# HDMI.net
KiCad netlist of a schematic drawn in Altium Designer
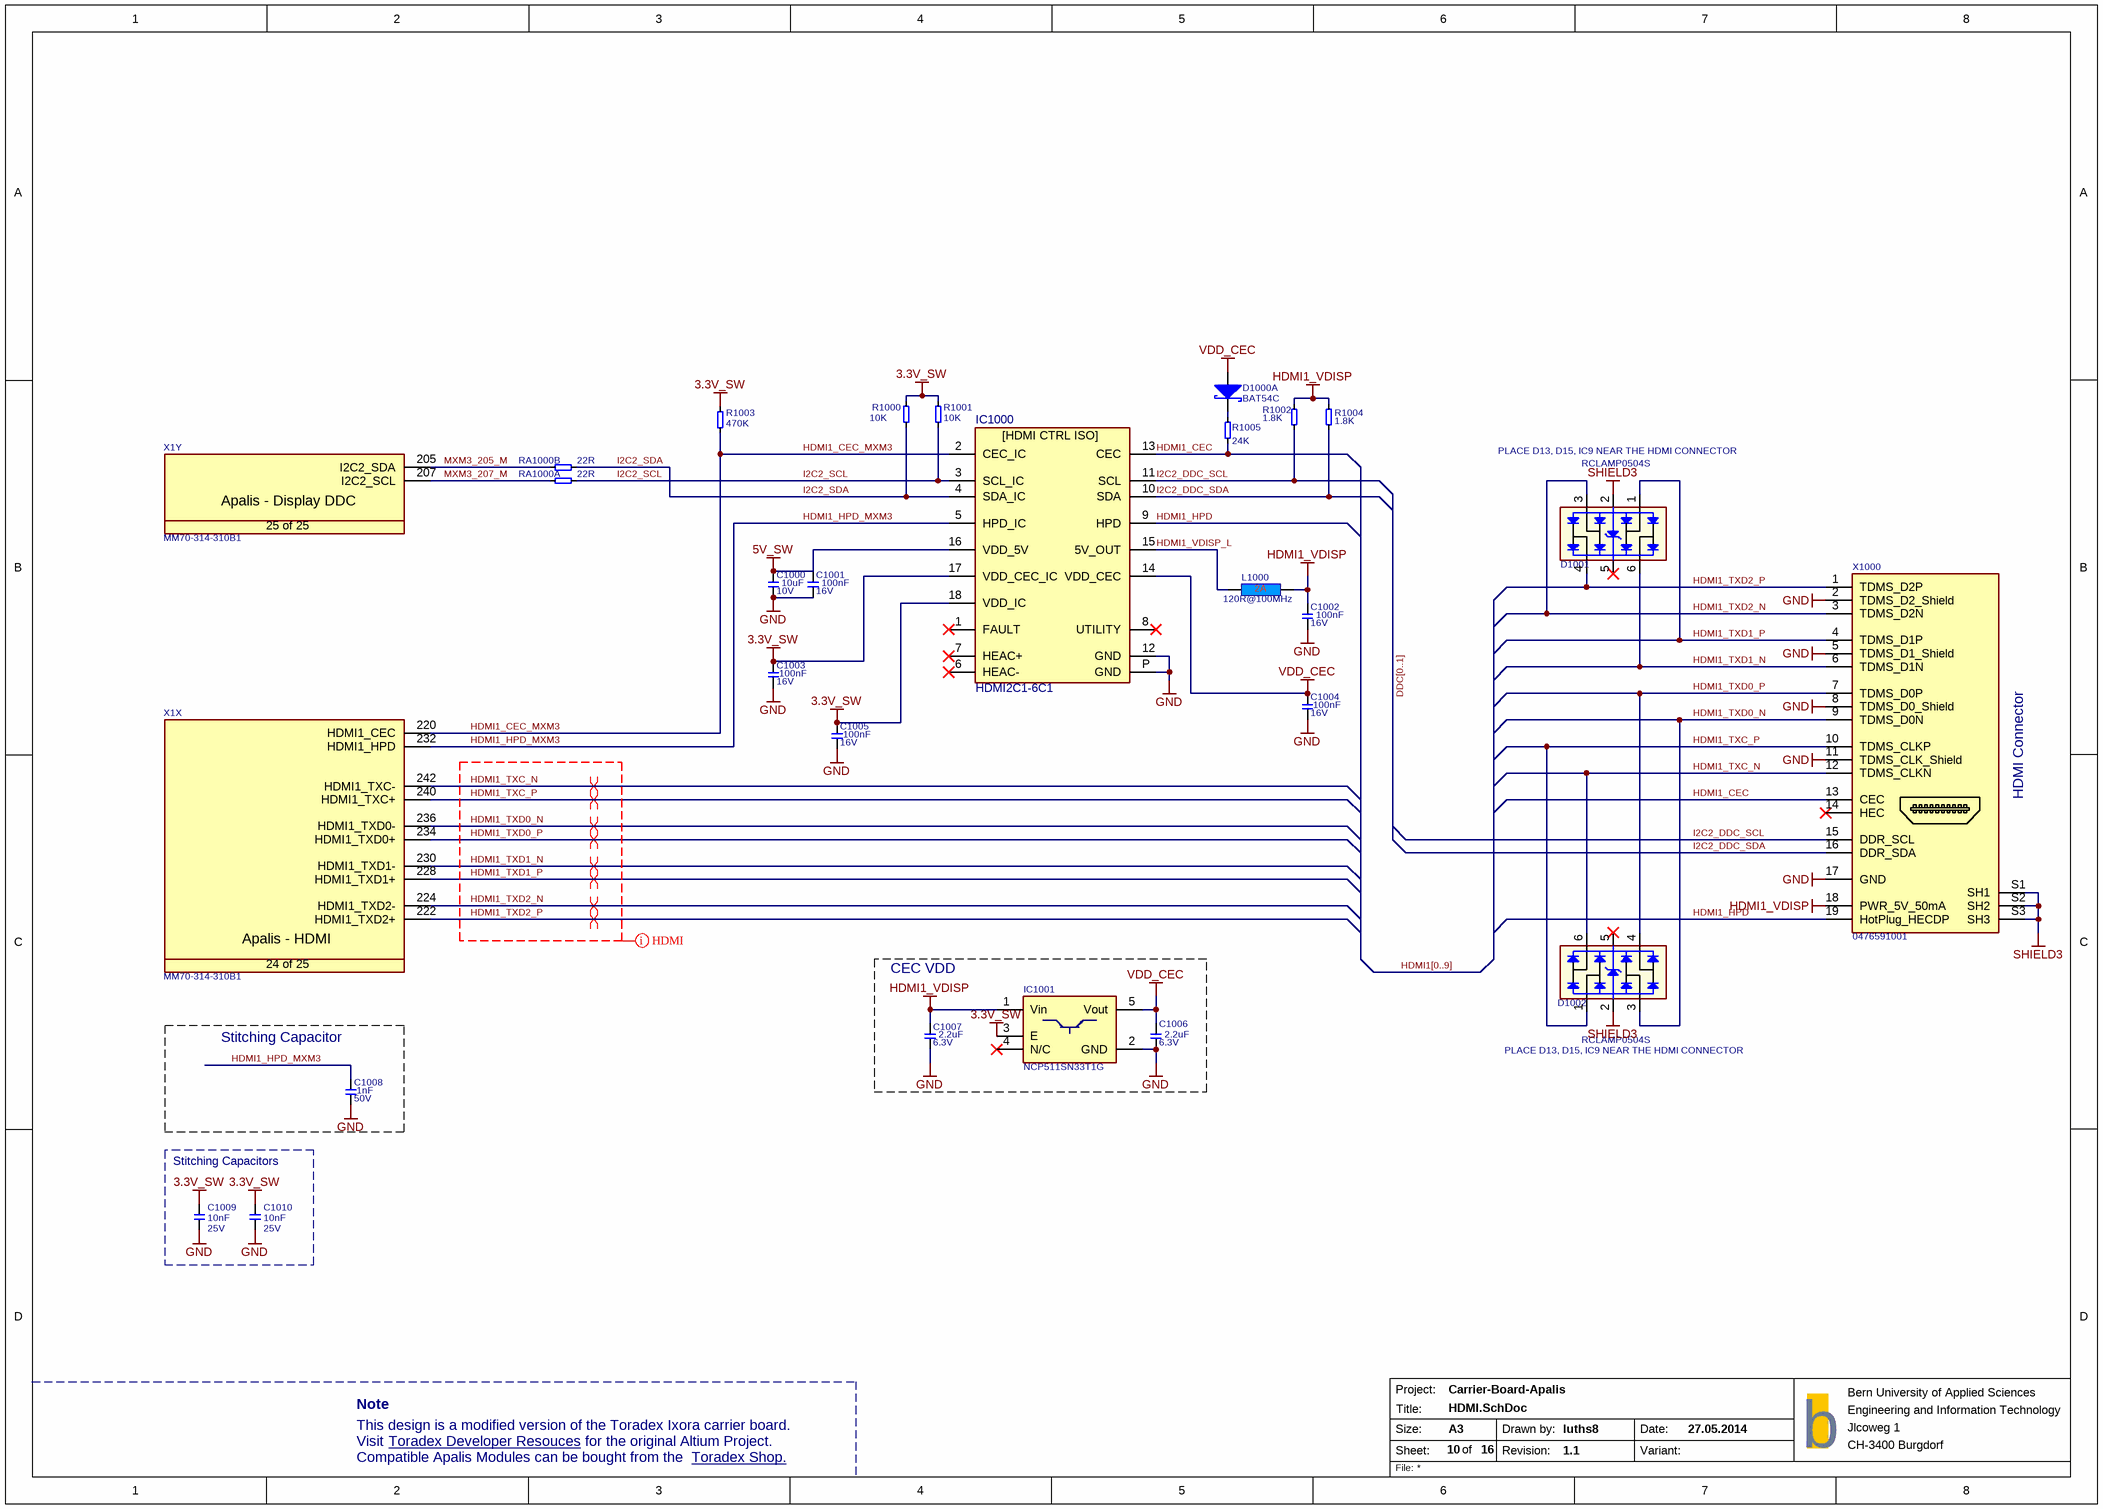
[diagram p0: HDMI.SchDoc]

(export (version "E")
  (design (tool "Eeschema 10.0.6"))
  (components
    (comp (ref "C1000")
      (value "10uF")
      (footprint "SMD0603CAP")
      (description "Capacitor Ceramic X5R 10uF 10V 20% 0603")
      (fields (field (name "TOLERANCE") "20%") (field (name "RATING") "10V"))
      (libsource (lib "Ixora") (part "C-X5R-10uF-10V-20%-0603"))
    )
    (comp (ref "C1001")
      (value "100nF")
      (footprint "SMD0603CAP")
      (description "Capacitor Ceramic X7R 100nF 16V 10% 0603")
      (fields (field (name "TOLERANCE") "10%") (field (name "RATING") "16V"))
      (libsource (lib "") (part "C-X7R-100nF-16V-10%-0402_1"))
    )
    (comp (ref "C1002")
      (value "100nF")
      (footprint "SMD0603CAP")
      (description "Capacitor Ceramic X7R 100nF 16V 10% 0603")
      (fields (field (name "TOLERANCE") "10%") (field (name "RATING") "16V"))
      (libsource (lib "Ixora") (part "C-X7R-100nF-16V-10%-0402"))
    )
    (comp (ref "C1003")
      (value "100nF")
      (footprint "SMD0603CAP")
      (description "Capacitor Ceramic X7R 100nF 16V 10% 0603")
      (fields (field (name "TOLERANCE") "10%") (field (name "RATING") "16V"))
      (libsource (lib "Ixora") (part "C-X7R-100nF-16V-10%-0402"))
    )
    (comp (ref "C1004")
      (value "100nF")
      (footprint "SMD0603CAP")
      (description "Capacitor Ceramic X7R 100nF 16V 10% 0603")
      (fields (field (name "TOLERANCE") "10%") (field (name "RATING") "16V"))
      (libsource (lib "Ixora") (part "C-X7R-100nF-16V-10%-0402"))
    )
    (comp (ref "C1005")
      (value "100nF")
      (footprint "SMD0603CAP")
      (description "Capacitor Ceramic X7R 100nF 16V 10% 0603")
      (fields (field (name "TOLERANCE") "10%") (field (name "RATING") "16V"))
      (libsource (lib "Ixora") (part "C-X7R-100nF-16V-10%-0402"))
    )
    (comp (ref "C1006")
      (value "2.2uF")
      (footprint "SMD0603CAP")
      (description "Capacitor Ceramic X5R 2.2uF 6.3V 20% 0603")
      (fields (field (name "TOLERANCE") "20%") (field (name "RATING") "6.3V"))
      (libsource (lib "Ixora") (part "C-X5R-2.2uF-6.3V-20%-0603"))
    )
    (comp (ref "C1007")
      (value "2.2uF")
      (footprint "SMD0603CAP")
      (description "Capacitor Ceramic X5R 2.2uF 6.3V 20% 0603")
      (fields (field (name "TOLERANCE") "20%") (field (name "RATING") "6.3V"))
      (libsource (lib "Ixora") (part "C-X5R-2.2uF-6.3V-20%-0603"))
    )
    (comp (ref "C1008")
      (value "1nF")
      (footprint "SMD0603CAP")
      (description "Capacitor Ceramic X7R 1nF 50V 10% 0603")
      (fields (field (name "TOLERANCE") "10%") (field (name "RATING") "50V"))
      (libsource (lib "Ixora") (part "C-X7R-1nF-50V-10%-0402"))
    )
    (comp (ref "C1009")
      (value "10nF")
      (footprint "SMD0603CAP")
      (description "Capacitor Ceramic X7R 10nF 25V 10% 0603")
      (fields (field (name "TOLERANCE") "10%") (field (name "RATING") "25V"))
      (libsource (lib "Ixora") (part "C-X7R-10nF-25V-10%-0603"))
    )
    (comp (ref "C1010")
      (value "10nF")
      (footprint "SMD0603CAP")
      (description "Capacitor Ceramic X7R 10nF 25V 10% 0603")
      (fields (field (name "TOLERANCE") "10%") (field (name "RATING") "25V"))
      (libsource (lib "Ixora") (part "C-X7R-10nF-25V-10%-0603"))
    )
    (comp (ref "D1000")
      (value "BAT54C")
      (footprint "SOT95P230X110-3N")
      (description "BAT54 Schottky Diode")
      (fields (field (name "MANUFACTURER") "Philips") (field (name "MANUFACTURER PART NUMBER") "BAT54C"))
      (libsource (lib "Ixora") (part "D-Philips-BAT54C-Schottky-30V-200mA"))
    )
    (comp (ref "D1001")
      (value "RCLAMP0504S")
      (footprint "T_SOT95P285X90-6N")
      (description "TVS Array low cap")
      (fields (field (name "MANUFACTURER PART NO.") "RCLAMP0504S"))
      (libsource (lib "") (part "D-Semtech-RClamp0504S_1"))
    )
    (comp (ref "D1002")
      (value "RCLAMP0504S")
      (footprint "T_SOT95P285X90-6N")
      (description "TVS Array low cap")
      (fields (field (name "MANUFACTURER PART NO.") "RCLAMP0504S"))
      (libsource (lib "Ixora") (part "D-Semtech-RClamp0504S"))
    )
    (comp (ref "IC1000")
      (value "HDMI2C1-6C1")
      (footprint "QFN18")
      (description "HDMI ESD protection, level shifter and backdrive protection")
      (libsource (lib "Audio-Streamer") (part "HDMI2C1-6C1"))
    )
    (comp (ref "IC1001")
      (value "NCP511SN33T1G")
      (footprint "SOT95P279X142-5N")
      (description "NCP511SN33T1G LDO Regulator")
      (fields (field (name "MANUFACTURER PART NO.") "NCP511SN33T1G"))
      (libsource (lib "Ixora") (part "IC-ON-NCP511SN33T1G"))
    )
    (comp (ref "L1000")
      (value "120R@100MHz")
      (footprint "INDC1608X95N")
      (description "120R@100MHz 2A EMI FILTER")
      (fields (field (name "TOLERANCE") "25%"))
      (libsource (lib "Ixora") (part "L-120R@100MHz-2A-25%-0603"))
    )
    (comp (ref "R1000")
      (value "10K")
      (footprint "SMD0603RES")
      (description "Resistor 10 Kohm 63mW 1% 0603")
      (fields (field (name "TOLERANCE") "1%"))
      (libsource (lib "Ixora") (part "R-10KR-63mW-1%-0603"))
    )
    (comp (ref "R1001")
      (value "10K")
      (footprint "SMD0603RES")
      (description "Resistor 10 Kohm 63mW 1% 0603")
      (fields (field (name "TOLERANCE") "1%"))
      (libsource (lib "Ixora") (part "R-10KR-63mW-1%-0603"))
    )
    (comp (ref "R1002")
      (value "1.8K")
      (footprint "SMD0603RES")
      (description "Resistor 1.8 Kohm 63mW 5% 0603")
      (fields (field (name "TOLERANCE") "5%"))
      (libsource (lib "Ixora") (part "R-1.8KR-63mW-5%-0603"))
    )
    (comp (ref "R1003")
      (value "470K")
      (footprint "SMD0603RES")
      (description "Resistor 470 Kohm 63mW 5% 0603")
      (fields (field (name "TOLERANCE") "5%"))
      (libsource (lib "Ixora") (part "R-470KR-63mW-5%-0402"))
    )
    (comp (ref "R1004")
      (value "1.8K")
      (footprint "SMD0603RES")
      (description "Resistor 1.8 Kohm 63mW 5% 0603")
      (fields (field (name "TOLERANCE") "5%"))
      (libsource (lib "Ixora") (part "R-1.8KR-63mW-5%-0603"))
    )
    (comp (ref "R1005")
      (value "24K")
      (footprint "SMD0603RES")
      (description "Resistor 24 Kohm 63mW 1% 0603")
      (fields (field (name "TOLERANCE") "1%"))
      (libsource (lib "Ixora") (part "R-24KR-63mW-1%-0402"))
    )
    (comp (ref "RA1000")
      (value "22R")
      (footprint "T_Resistor_Array_X4")
      (description "Resistor Array 22 R 63mW 5% 1206")
      (fields (field (name "TOLERANCE") "5%"))
      (libsource (lib "Ixora") (part "RA-22R-63mW-5%-1206-div"))
    )
    (comp (ref "X1")
      (value "CON-JAE-MM70-314-310B1-314-0.5mm")
      (footprint "T_JAE_MM70-314-310B1")
      (description "MXM3 Connector")
      (fields (field (name "MANUFACTURER PART NO.") "MM70-314-310B1"))
      (libsource (lib "") (part "CON-JAE-MM70-314-310B1-314-0.5mm_1"))
    )
    (comp (ref "X1000")
      (value "0476591001")
      (footprint "0476591001")
      (description "HDMI Connector Vertical")
      (fields (field (name "MANUFACTURER") "Molex") (field (name "MANUFACTURER PART NO.") "0476591001"))
      (libsource (lib "Ixora") (part "CON-Molex-0476591001"))
    )
  )
  (nets
    (net (code "15") (name "/HDMI1_CEC") (class "Default")
      (node (ref "IC1000") (pin "13") (pinfunction "CEC_13") (pintype "passive"))
      (node (ref "R1005") (pin "1") (pinfunction "1_1") (pintype "passive"))
      (node (ref "X1000") (pin "13") (pinfunction "CEC_13") (pintype "passive"))
    )
    (net (code "16") (name "/HDMI1_CEC_MXM3") (class "Default")
      (node (ref "IC1000") (pin "2") (pinfunction "CEC_IC_2") (pintype "passive"))
      (node (ref "R1003") (pin "1") (pinfunction "1_1") (pintype "passive"))
      (node (ref "X1") (pin "220") (pinfunction "HDMI1_CEC_220") (pintype "passive"))
    )
    (net (code "17") (name "/HDMI1_HPD") (class "Default")
      (node (ref "IC1000") (pin "9") (pinfunction "HPD_9") (pintype "passive"))
      (node (ref "X1000") (pin "19") (pinfunction "HotPlug_HECDP_19") (pintype "passive"))
    )
    (net (code "18") (name "/HDMI1_HPD_MXM3") (class "Default")
      (node (ref "C1008") (pin "2") (pinfunction "2_2") (pintype "passive"))
      (node (ref "IC1000") (pin "5") (pinfunction "HPD_IC_5") (pintype "passive"))
      (node (ref "X1") (pin "232") (pinfunction "HDMI1_HPD_232") (pintype "passive"))
    )
    (net (code "19") (name "/HDMI1_TXC_N") (class "Default")
      (node (ref "D1002") (pin "6") (pinfunction "6_6") (pintype "power_in"))
      (node (ref "X1") (pin "242") (pinfunction "HDMI1_TXC-_242") (pintype "passive"))
      (node (ref "X1000") (pin "12") (pinfunction "TDMS_CLKN_12") (pintype "passive"))
    )
    (net (code "20") (name "/HDMI1_TXC_P") (class "Default")
      (node (ref "D1002") (pin "1") (pinfunction "1_1") (pintype "power_in"))
      (node (ref "X1") (pin "240") (pinfunction "HDMI1_TXC+_240") (pintype "passive"))
      (node (ref "X1000") (pin "10") (pinfunction "TDMS_CLKP_10") (pintype "passive"))
    )
    (net (code "21") (name "/HDMI1_TXD0_N") (class "Default")
      (node (ref "D1002") (pin "3") (pinfunction "3_3") (pintype "power_in"))
      (node (ref "X1") (pin "236") (pinfunction "HDMI1_TXD0-_236") (pintype "passive"))
      (node (ref "X1000") (pin "9") (pinfunction "TDMS_D0N_9") (pintype "passive"))
    )
    (net (code "22") (name "/HDMI1_TXD0_P") (class "Default")
      (node (ref "D1002") (pin "4") (pinfunction "4_4") (pintype "power_in"))
      (node (ref "X1") (pin "234") (pinfunction "HDMI1_TXD0+_234") (pintype "passive"))
      (node (ref "X1000") (pin "7") (pinfunction "TDMS_D0P_7") (pintype "passive"))
    )
    (net (code "23") (name "/HDMI1_TXD1_N") (class "Default")
      (node (ref "D1001") (pin "6") (pinfunction "6_6") (pintype "power_in"))
      (node (ref "X1") (pin "230") (pinfunction "HDMI1_TXD1-_230") (pintype "passive"))
      (node (ref "X1000") (pin "6") (pinfunction "TDMS_D1N_6") (pintype "passive"))
    )
    (net (code "24") (name "/HDMI1_TXD1_P") (class "Default")
      (node (ref "D1001") (pin "1") (pinfunction "1_1") (pintype "power_in"))
      (node (ref "X1") (pin "228") (pinfunction "HDMI1_TXD1+_228") (pintype "passive"))
      (node (ref "X1000") (pin "4") (pinfunction "TDMS_D1P_4") (pintype "passive"))
    )
    (net (code "25") (name "/HDMI1_TXD2_N") (class "Default")
      (node (ref "D1001") (pin "3") (pinfunction "3_3") (pintype "power_in"))
      (node (ref "X1") (pin "224") (pinfunction "HDMI1_TXD2-_224") (pintype "passive"))
      (node (ref "X1000") (pin "3") (pinfunction "TDMS_D2N_3") (pintype "passive"))
    )
    (net (code "26") (name "/HDMI1_TXD2_P") (class "Default")
      (node (ref "D1001") (pin "4") (pinfunction "4_4") (pintype "power_in"))
      (node (ref "X1") (pin "222") (pinfunction "HDMI1_TXD2+_222") (pintype "passive"))
      (node (ref "X1000") (pin "1") (pinfunction "TDMS_D2P_1") (pintype "passive"))
    )
    (net (code "28") (name "/I2C2_DDC_SCL") (class "Default")
      (node (ref "IC1000") (pin "11") (pinfunction "SCL_11") (pintype "passive"))
      (node (ref "R1002") (pin "1") (pinfunction "1_1") (pintype "passive"))
      (node (ref "X1000") (pin "15") (pinfunction "DDR_SCL_15") (pintype "passive"))
    )
    (net (code "29") (name "/I2C2_DDC_SDA") (class "Default")
      (node (ref "IC1000") (pin "10") (pinfunction "SDA_10") (pintype "passive"))
      (node (ref "R1004") (pin "1") (pinfunction "1_1") (pintype "passive"))
      (node (ref "X1000") (pin "16") (pinfunction "DDR_SDA_16") (pintype "passive"))
    )
    (net (code "30") (name "/I2C2_SCL") (class "Default")
      (node (ref "IC1000") (pin "3") (pinfunction "SCL_IC_3") (pintype "passive"))
      (node (ref "R1001") (pin "1") (pinfunction "1_1") (pintype "passive"))
      (node (ref "RA1000") (pin "5") (pinfunction "5_5") (pintype "passive"))
    )
    (net (code "31") (name "/I2C2_SDA") (class "Default")
      (node (ref "IC1000") (pin "4") (pinfunction "SDA_IC_4") (pintype "passive"))
      (node (ref "R1000") (pin "1") (pinfunction "1_1") (pintype "passive"))
      (node (ref "RA1000") (pin "6") (pinfunction "6_6") (pintype "passive"))
    )
    (net (code "32") (name "/MXM3_205_M") (class "Default")
      (node (ref "RA1000") (pin "2") (pinfunction "2_2") (pintype "passive"))
      (node (ref "X1") (pin "205") (pinfunction "I2C2_SDA_205") (pintype "passive"))
    )
    (net (code "33") (name "/MXM3_207_M") (class "Default")
      (node (ref "RA1000") (pin "1") (pinfunction "1_1") (pintype "passive"))
      (node (ref "X1") (pin "207") (pinfunction "I2C2_SCL_207") (pintype "passive"))
    )
    (net (code "34") (name "3.3V_SW") (class "Default")
      (node (ref "C1003") (pin "2") (pinfunction "2_2") (pintype "passive"))
      (node (ref "C1005") (pin "2") (pinfunction "2_2") (pintype "passive"))
      (node (ref "C1009") (pin "2") (pinfunction "2_2") (pintype "passive"))
      (node (ref "C1010") (pin "2") (pinfunction "2_2") (pintype "passive"))
      (node (ref "IC1000") (pin "17") (pinfunction "VDD_CEC_IC_17") (pintype "passive"))
      (node (ref "IC1000") (pin "18") (pinfunction "VDD_IC_18") (pintype "passive"))
      (node (ref "IC1001") (pin "3") (pinfunction "E_3") (pintype "passive"))
      (node (ref "R1000") (pin "2") (pinfunction "2_2") (pintype "passive"))
      (node (ref "R1001") (pin "2") (pinfunction "2_2") (pintype "passive"))
      (node (ref "R1003") (pin "2") (pinfunction "2_2") (pintype "passive"))
    )
    (net (code "35") (name "5V_SW") (class "Default")
      (node (ref "C1000") (pin "2") (pinfunction "2_2") (pintype "passive"))
      (node (ref "C1001") (pin "1") (pinfunction "1_1") (pintype "passive"))
      (node (ref "IC1000") (pin "16") (pinfunction "VDD_5V_16") (pintype "passive"))
    )
    (net (code "36") (name "GND") (class "Default")
      (node (ref "C1000") (pin "1") (pinfunction "1_1") (pintype "passive"))
      (node (ref "C1001") (pin "2") (pinfunction "2_2") (pintype "passive"))
      (node (ref "C1002") (pin "1") (pinfunction "1_1") (pintype "passive"))
      (node (ref "C1003") (pin "1") (pinfunction "1_1") (pintype "passive"))
      (node (ref "C1004") (pin "1") (pinfunction "1_1") (pintype "passive"))
      (node (ref "C1005") (pin "1") (pinfunction "1_1") (pintype "passive"))
      (node (ref "C1006") (pin "1") (pinfunction "1_1") (pintype "passive"))
      (node (ref "C1007") (pin "1") (pinfunction "1_1") (pintype "passive"))
      (node (ref "C1008") (pin "1") (pinfunction "1_1") (pintype "passive"))
      (node (ref "C1009") (pin "1") (pinfunction "1_1") (pintype "passive"))
      (node (ref "C1010") (pin "1") (pinfunction "1_1") (pintype "passive"))
      (node (ref "IC1000") (pin "12") (pinfunction "GND_12") (pintype "passive"))
      (node (ref "IC1000") (pin "P") (pinfunction "GND_P") (pintype "passive"))
      (node (ref "IC1001") (pin "2") (pinfunction "GND_2") (pintype "passive"))
      (node (ref "X1000") (pin "11") (pinfunction "TDMS_CLK_Shield_11") (pintype "passive"))
      (node (ref "X1000") (pin "17") (pinfunction "GND_17") (pintype "passive"))
      (node (ref "X1000") (pin "2") (pinfunction "TDMS_D2_Shield_2") (pintype "passive"))
      (node (ref "X1000") (pin "5") (pinfunction "TDMS_D1_Shield_5") (pintype "passive"))
      (node (ref "X1000") (pin "8") (pinfunction "TDMS_D0_Shield_8") (pintype "passive"))
    )
    (net (code "37") (name "HDMI1_VDISP") (class "Default")
      (node (ref "C1002") (pin "2") (pinfunction "2_2") (pintype "passive"))
      (node (ref "C1007") (pin "2") (pinfunction "2_2") (pintype "passive"))
      (node (ref "IC1001") (pin "1") (pinfunction "Vin_1") (pintype "passive"))
      (node (ref "L1000") (pin "2") (pinfunction "2_2") (pintype "passive"))
      (node (ref "R1002") (pin "2") (pinfunction "2_2") (pintype "passive"))
      (node (ref "R1004") (pin "2") (pinfunction "2_2") (pintype "passive"))
      (node (ref "X1000") (pin "18") (pinfunction "PWR_5V_50mA_18") (pintype "passive"))
    )
    (net (code "38") (name "Net-(D1000-Pad3)") (class "Default")
      (node (ref "D1000") (pin "3") (pinfunction "3_3") (pintype "passive"))
      (node (ref "R1005") (pin "2") (pinfunction "2_2") (pintype "passive"))
    )
    (net (code "39") (name "Net-(IC1000-5V_OUT)") (class "Default")
      (node (ref "IC1000") (pin "15") (pinfunction "5V_OUT_15") (pintype "passive"))
      (node (ref "L1000") (pin "1") (pinfunction "1_1") (pintype "passive"))
    )
    (net (code "40") (name "SHIELD3") (class "Default")
      (node (ref "D1001") (pin "2") (pinfunction "2_2") (pintype "power_in"))
      (node (ref "D1002") (pin "2") (pinfunction "2_2") (pintype "power_in"))
      (node (ref "X1000") (pin "S1") (pinfunction "SH1_S1") (pintype "passive"))
      (node (ref "X1000") (pin "S2") (pinfunction "SH2_S2") (pintype "passive"))
      (node (ref "X1000") (pin "S3") (pinfunction "SH3_S3") (pintype "passive"))
    )
    (net (code "41") (name "VDD_CEC") (class "Default")
      (node (ref "C1004") (pin "2") (pinfunction "2_2") (pintype "passive"))
      (node (ref "C1006") (pin "2") (pinfunction "2_2") (pintype "passive"))
      (node (ref "D1000") (pin "1") (pinfunction "1_1") (pintype "passive"))
      (node (ref "IC1000") (pin "14") (pinfunction "VDD_CEC_14") (pintype "passive"))
      (node (ref "IC1001") (pin "5") (pinfunction "Vout_5") (pintype "passive"))
    )
    (net (code "42") (name "unconnected-(D1001-Pad5)") (class "Default")
      (node (ref "D1001") (pin "5") (pinfunction "5_5") (pintype "power_in+no_connect"))
    )
    (net (code "43") (name "unconnected-(D1002-Pad5)") (class "Default")
      (node (ref "D1002") (pin "5") (pinfunction "5_5") (pintype "power_in+no_connect"))
    )
    (net (code "44") (name "unconnected-(IC1000-FAULT-Pad1)") (class "Default")
      (node (ref "IC1000") (pin "1") (pinfunction "FAULT_1") (pintype "passive+no_connect"))
    )
    (net (code "45") (name "unconnected-(IC1000-HEAC+-Pad7)") (class "Default")
      (node (ref "IC1000") (pin "7") (pinfunction "HEAC+_7") (pintype "passive+no_connect"))
    )
    (net (code "46") (name "unconnected-(IC1000-HEAC--Pad6)") (class "Default")
      (node (ref "IC1000") (pin "6") (pinfunction "HEAC-_6") (pintype "passive+no_connect"))
    )
    (net (code "47") (name "unconnected-(IC1000-UTILITY-Pad8)") (class "Default")
      (node (ref "IC1000") (pin "8") (pinfunction "UTILITY_8") (pintype "passive+no_connect"))
    )
    (net (code "48") (name "unconnected-(IC1001-N{slash}C-Pad4)") (class "Default")
      (node (ref "IC1001") (pin "4") (pinfunction "N/C_4") (pintype "passive+no_connect"))
    )
    (net (code "49") (name "unconnected-(X1000-HEC-Pad14)") (class "Default")
      (node (ref "X1000") (pin "14") (pinfunction "HEC_14") (pintype "passive+no_connect"))
    )
  )
)
